# Sheme_PowerOutPut.net
KiCad netlist of a schematic drawn in Altium Designer
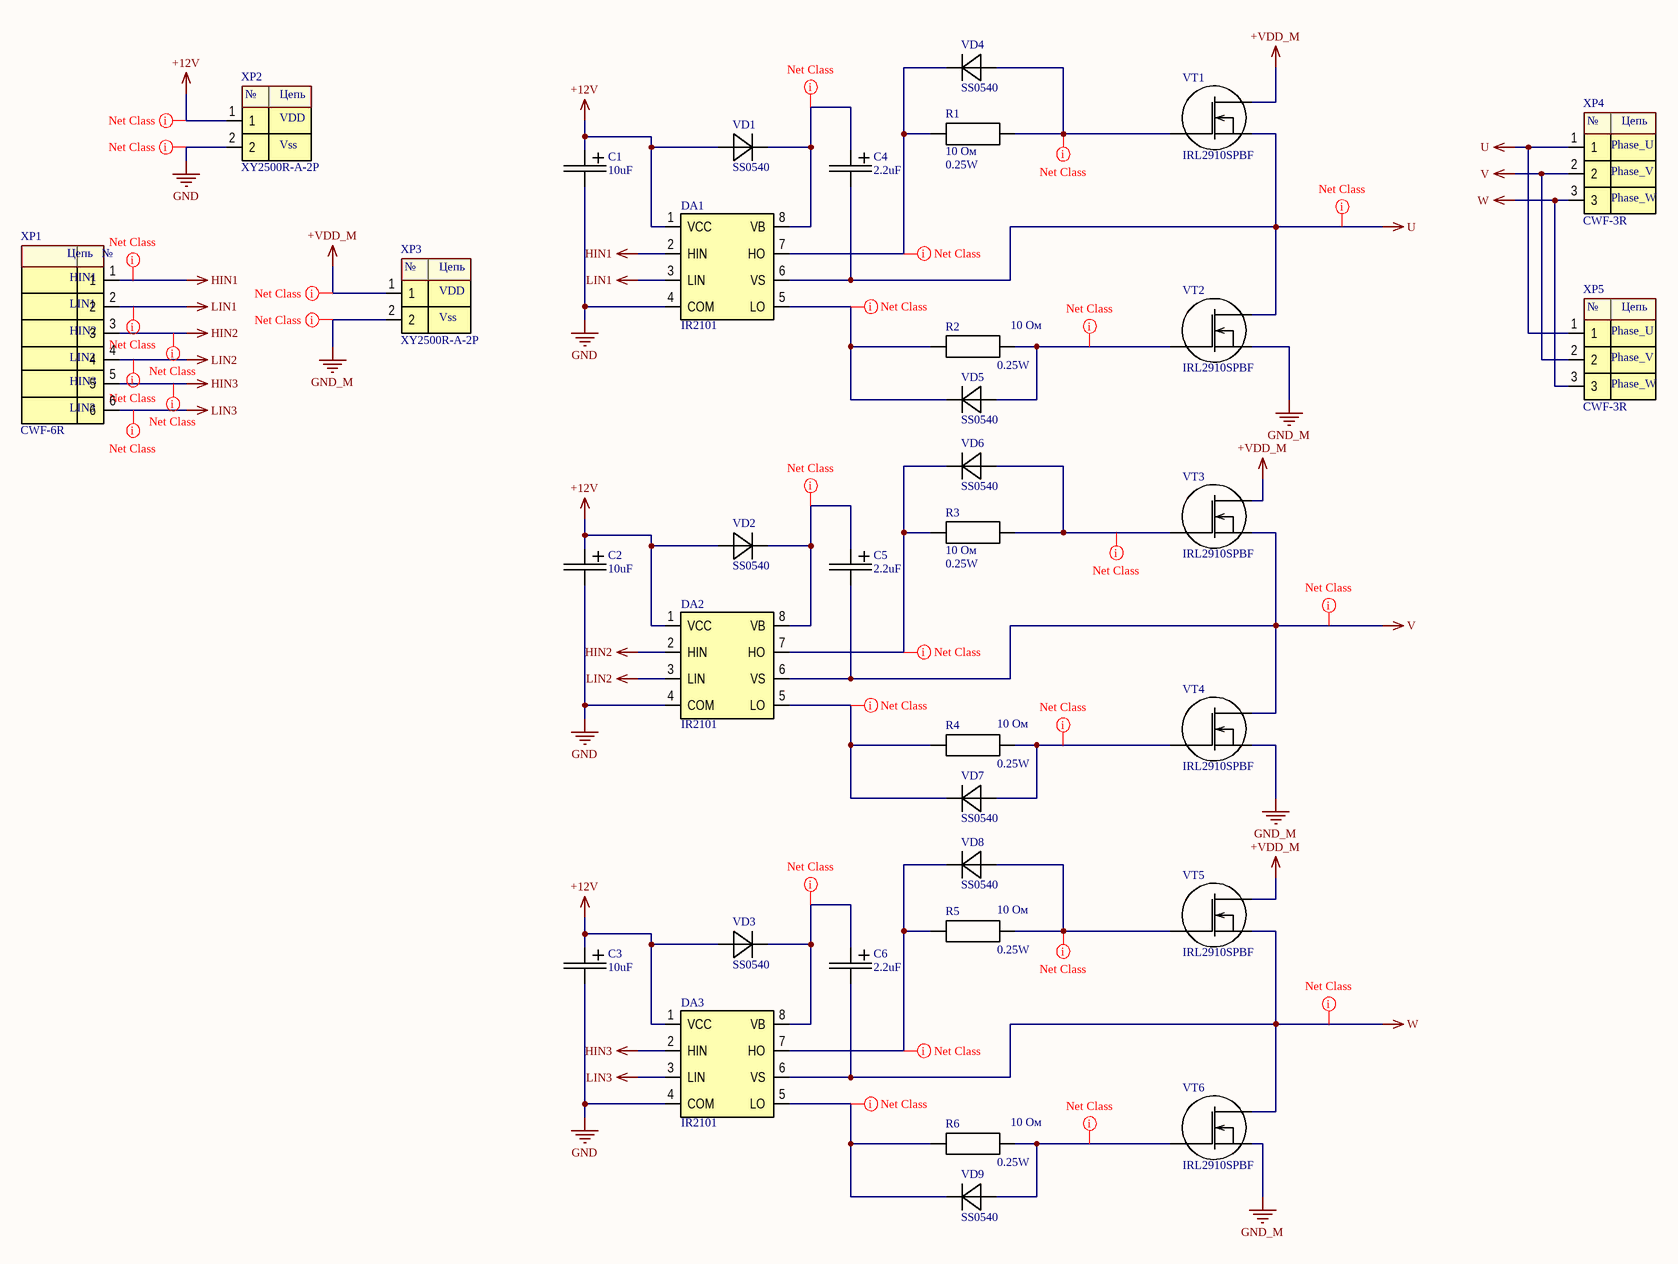
[diagram p0: Sheme_PowerOutPut.SchDoc]

(export (version "E")
  (design (tool "Eeschema 10.0.6"))
  (components
    (comp (ref "C1")
      (value "10uF")
      (footprint "CAPTtantaltypeA")
      (fields
        (field (name "PART NUMBER") "TA2u2")
        (field (name "MANUFACTURER") "Samsung")
        (field (name "POWER") "16V")
      )
      (libsource (lib "SchlibUGO") (part "Capasitor Electrolit"))
    )
    (comp (ref "C2")
      (value "10uF")
      (footprint "CAPTtantaltypeA")
      (fields
        (field (name "PART NUMBER") "TA2u2")
        (field (name "MANUFACTURER") "Samsung")
        (field (name "POWER") "16V")
      )
      (libsource (lib "SchlibUGO") (part "Capasitor Electrolit"))
    )
    (comp (ref "C3")
      (value "10uF")
      (footprint "CAPTtantaltypeA")
      (fields
        (field (name "PART NUMBER") "TA2u2")
        (field (name "MANUFACTURER") "Samsung")
        (field (name "POWER") "16V")
      )
      (libsource (lib "SchlibUGO") (part "Capasitor Electrolit"))
    )
    (comp (ref "C4")
      (value "2.2uF")
      (footprint "CAPTtantaltypeA")
      (fields
        (field (name "PART NUMBER") "TA2u2")
        (field (name "MANUFACTURER") "Samsung")
        (field (name "POWER") "16V")
      )
      (libsource (lib "SchlibUGO") (part "Capasitor Electrolit"))
    )
    (comp (ref "C5")
      (value "2.2uF")
      (footprint "CAPTtantaltypeA")
      (fields
        (field (name "PART NUMBER") "TA2u2")
        (field (name "MANUFACTURER") "Samsung")
        (field (name "POWER") "16V")
      )
      (libsource (lib "SchlibUGO") (part "Capasitor Electrolit"))
    )
    (comp (ref "C6")
      (value "2.2uF")
      (footprint "CAPTtantaltypeA")
      (fields
        (field (name "PART NUMBER") "TA2u2")
        (field (name "MANUFACTURER") "Samsung")
        (field (name "POWER") "16V")
      )
      (libsource (lib "SchlibUGO") (part "Capasitor Electrolit"))
    )
    (comp (ref "DA1")
      (value "IR2101")
      (footprint "SO-8")
      (fields (field (name "PART NUMBER") "IR2101SPBF"))
      (libsource (lib "SchlibUGO") (part "IR2101"))
    )
    (comp (ref "DA2")
      (value "IR2101")
      (footprint "SO-8")
      (fields (field (name "PART NUMBER") "IR2101SPBF"))
      (libsource (lib "SchlibUGO") (part "IR2101"))
    )
    (comp (ref "DA3")
      (value "IR2101")
      (footprint "SO-8")
      (fields (field (name "PART NUMBER") "IR2101SPBF"))
      (libsource (lib "SchlibUGO") (part "IR2101"))
    )
    (comp (ref "R1")
      (value "10 Ом")
      (footprint "1206")
      (fields
        (field (name "MANUFACTURER") "YAGEO")
        (field (name "PART NUMBER") "RC1206JR-0710RL")
        (field (name "POWER") "0.25W")
      )
      (libsource (lib "SchlibUGO") (part "Resistor"))
    )
    (comp (ref "R2")
      (value "10 Ом")
      (footprint "1206")
      (fields
        (field (name "MANUFACTURER") "YAGEO")
        (field (name "PART NUMBER") "RC1206JR-0710RL")
        (field (name "POWER") "0.25W")
      )
      (libsource (lib "SchlibUGO") (part "Resistor"))
    )
    (comp (ref "R3")
      (value "10 Ом")
      (footprint "1206")
      (fields
        (field (name "MANUFACTURER") "YAGEO")
        (field (name "PART NUMBER") "RC1206JR-0710RL")
        (field (name "POWER") "0.25W")
      )
      (libsource (lib "SchlibUGO") (part "Resistor"))
    )
    (comp (ref "R4")
      (value "10 Ом")
      (footprint "1206")
      (fields
        (field (name "MANUFACTURER") "YAGEO")
        (field (name "PART NUMBER") "RC1206JR-0710RL")
        (field (name "POWER") "0.25W")
      )
      (libsource (lib "SchlibUGO") (part "Resistor"))
    )
    (comp (ref "R5")
      (value "10 Ом")
      (footprint "1206")
      (fields
        (field (name "MANUFACTURER") "YAGEO")
        (field (name "PART NUMBER") "RC1206JR-0710RL")
        (field (name "POWER") "0.25W")
      )
      (libsource (lib "SchlibUGO") (part "Resistor"))
    )
    (comp (ref "R6")
      (value "10 Ом")
      (footprint "1206")
      (fields
        (field (name "MANUFACTURER") "YAGEO")
        (field (name "PART NUMBER") "RC1206JR-0710RL")
        (field (name "POWER") "0.25W")
      )
      (libsource (lib "SchlibUGO") (part "Resistor"))
    )
    (comp (ref "VD1")
      (value "SS0540")
      (footprint "SOD-123")
      (fields (field (name "MANUFACTURER") "DC Components"))
      (libsource (lib "SchlibUGO") (part "SS0540"))
    )
    (comp (ref "VD2")
      (value "SS0540")
      (footprint "SOD-123")
      (fields (field (name "MANUFACTURER") "DC Components"))
      (libsource (lib "SchlibUGO") (part "SS0540"))
    )
    (comp (ref "VD3")
      (value "SS0540")
      (footprint "SOD-123")
      (fields (field (name "MANUFACTURER") "DC Components"))
      (libsource (lib "SchlibUGO") (part "SS0540"))
    )
    (comp (ref "VD4")
      (value "SS0540")
      (footprint "SOD-123")
      (fields (field (name "MANUFACTURER") "DC Components"))
      (libsource (lib "SchlibUGO") (part "SS0540"))
    )
    (comp (ref "VD5")
      (value "SS0540")
      (footprint "SOD-123")
      (fields (field (name "MANUFACTURER") "DC Components"))
      (libsource (lib "SchlibUGO") (part "SS0540"))
    )
    (comp (ref "VD6")
      (value "SS0540")
      (footprint "SOD-123")
      (fields (field (name "MANUFACTURER") "DC Components"))
      (libsource (lib "SchlibUGO") (part "SS0540"))
    )
    (comp (ref "VD7")
      (value "SS0540")
      (footprint "SOD-123")
      (fields (field (name "MANUFACTURER") "DC Components"))
      (libsource (lib "SchlibUGO") (part "SS0540"))
    )
    (comp (ref "VD8")
      (value "SS0540")
      (footprint "SOD-123")
      (fields (field (name "MANUFACTURER") "DC Components"))
      (libsource (lib "SchlibUGO") (part "SS0540"))
    )
    (comp (ref "VD9")
      (value "SS0540")
      (footprint "SOD-123")
      (fields (field (name "MANUFACTURER") "DC Components"))
      (libsource (lib "SchlibUGO") (part "SS0540"))
    )
    (comp (ref "VT1")
      (value "IRL2910SPBF")
      (footprint "D2PACK")
      (fields (field (name "MANUFACTURER") "International rectifier"))
      (libsource (lib "SchlibUGO") (part "IRL2910SPBF"))
    )
    (comp (ref "VT2")
      (value "IRL2910SPBF")
      (footprint "D2PACK")
      (fields (field (name "MANUFACTURER") "International rectifier"))
      (libsource (lib "SchlibUGO") (part "IRL2910SPBF"))
    )
    (comp (ref "VT3")
      (value "IRL2910SPBF")
      (footprint "D2PACK")
      (fields (field (name "MANUFACTURER") "International rectifier"))
      (libsource (lib "SchlibUGO") (part "IRL2910SPBF"))
    )
    (comp (ref "VT4")
      (value "IRL2910SPBF")
      (footprint "D2PACK")
      (fields (field (name "MANUFACTURER") "International rectifier"))
      (libsource (lib "SchlibUGO") (part "IRL2910SPBF"))
    )
    (comp (ref "VT5")
      (value "IRL2910SPBF")
      (footprint "D2PACK")
      (fields (field (name "MANUFACTURER") "International rectifier"))
      (libsource (lib "SchlibUGO") (part "IRL2910SPBF"))
    )
    (comp (ref "VT6")
      (value "IRL2910SPBF")
      (footprint "D2PACK")
      (fields (field (name "MANUFACTURER") "International rectifier"))
      (libsource (lib "SchlibUGO") (part "IRL2910SPBF"))
    )
    (comp (ref "XP1")
      (value "CWF-6R")
      (footprint "CWF-6R")
      (fields (field (name "MANUFACTURER") "KLS"))
      (libsource (lib "SchlibUGO") (part "CWF-6R"))
    )
    (comp (ref "XP2")
      (value "XY2500R-A-2P")
      (footprint "KLS2-EDR-500-2P")
      (fields (field (name "MANUFACTURER") "RoB"))
      (libsource (lib "SchlibUGO") (part "Connector_Power"))
    )
    (comp (ref "XP3")
      (value "XY2500R-A-2P")
      (footprint "KLS2-EDR-500-2P")
      (fields (field (name "MANUFACTURER") "RoB"))
      (libsource (lib "SchlibUGO") (part "Connector_Power"))
    )
    (comp (ref "XP4")
      (value "CWF-3R")
      (footprint "CWF-3R")
      (fields (field (name "MANUFACTURER") "KLS"))
      (libsource (lib "SchlibUGO") (part "CWF-3R"))
    )
    (comp (ref "XP5")
      (value "CWF-3R")
      (footprint "CWF-3R")
      (fields (field (name "MANUFACTURER") "KLS"))
      (libsource (lib "SchlibUGO") (part "CWF-3R"))
    )
  )
  (nets
    (net (code "1") (name "+12V") (class "Default")
      (node (ref "C1") (pin "1") (pinfunction "1_1") (pintype "passive"))
      (node (ref "C2") (pin "1") (pinfunction "1_1") (pintype "passive"))
      (node (ref "C3") (pin "1") (pinfunction "1_1") (pintype "passive"))
      (node (ref "DA1") (pin "1") (pinfunction "VCC_1") (pintype "passive"))
      (node (ref "DA2") (pin "1") (pinfunction "VCC_1") (pintype "passive"))
      (node (ref "DA3") (pin "1") (pinfunction "VCC_1") (pintype "passive"))
      (node (ref "VD1") (pin "1") (pinfunction "1_1") (pintype "passive"))
      (node (ref "VD2") (pin "1") (pinfunction "1_1") (pintype "passive"))
      (node (ref "VD3") (pin "1") (pinfunction "1_1") (pintype "passive"))
      (node (ref "XP2") (pin "1") (pinfunction "1_1") (pintype "passive"))
    )
    (net (code "2") (name "+VDD_M") (class "Default")
      (node (ref "VT1") (pin "2") (pinfunction "D_2") (pintype "passive"))
      (node (ref "VT3") (pin "2") (pinfunction "D_2") (pintype "passive"))
      (node (ref "VT5") (pin "2") (pinfunction "D_2") (pintype "passive"))
      (node (ref "XP3") (pin "1") (pinfunction "1_1") (pintype "passive"))
    )
    (net (code "3") (name "GND") (class "Default")
      (node (ref "C1") (pin "2") (pinfunction "2_2") (pintype "passive"))
      (node (ref "C2") (pin "2") (pinfunction "2_2") (pintype "passive"))
      (node (ref "C3") (pin "2") (pinfunction "2_2") (pintype "passive"))
      (node (ref "DA1") (pin "4") (pinfunction "COM_4") (pintype "passive"))
      (node (ref "DA2") (pin "4") (pinfunction "COM_4") (pintype "passive"))
      (node (ref "DA3") (pin "4") (pinfunction "COM_4") (pintype "passive"))
      (node (ref "XP2") (pin "2") (pinfunction "2_2") (pintype "passive"))
    )
    (net (code "4") (name "GND_M") (class "Default")
      (node (ref "VT2") (pin "3") (pinfunction "Source_3") (pintype "passive"))
      (node (ref "VT4") (pin "3") (pinfunction "Source_3") (pintype "passive"))
      (node (ref "VT6") (pin "3") (pinfunction "Source_3") (pintype "passive"))
      (node (ref "XP3") (pin "2") (pinfunction "2_2") (pintype "passive"))
    )
    (net (code "5") (name "HIN1") (class "Default")
      (node (ref "DA1") (pin "2") (pinfunction "HIN_2") (pintype "passive"))
      (node (ref "XP1") (pin "1") (pinfunction "1_1") (pintype "passive"))
    )
    (net (code "6") (name "HIN2") (class "Default")
      (node (ref "DA2") (pin "2") (pinfunction "HIN_2") (pintype "passive"))
      (node (ref "XP1") (pin "3") (pinfunction "3_3") (pintype "passive"))
    )
    (net (code "7") (name "HIN3") (class "Default")
      (node (ref "DA3") (pin "2") (pinfunction "HIN_2") (pintype "passive"))
      (node (ref "XP1") (pin "5") (pinfunction "5_5") (pintype "passive"))
    )
    (net (code "8") (name "LIN1") (class "Default")
      (node (ref "DA1") (pin "3") (pinfunction "LIN_3") (pintype "passive"))
      (node (ref "XP1") (pin "2") (pinfunction "2_2") (pintype "passive"))
    )
    (net (code "9") (name "LIN2") (class "Default")
      (node (ref "DA2") (pin "3") (pinfunction "LIN_3") (pintype "passive"))
      (node (ref "XP1") (pin "4") (pinfunction "4_4") (pintype "passive"))
    )
    (net (code "10") (name "LIN3") (class "Default")
      (node (ref "DA3") (pin "3") (pinfunction "LIN_3") (pintype "passive"))
      (node (ref "XP1") (pin "6") (pinfunction "6_6") (pintype "passive"))
    )
    (net (code "11") (name "Net-(DA1-HO)") (class "Default")
      (node (ref "DA1") (pin "7") (pinfunction "HO_7") (pintype "passive"))
      (node (ref "R1") (pin "1") (pinfunction "1_1") (pintype "passive"))
      (node (ref "VD4") (pin "2") (pinfunction "2_2") (pintype "passive"))
    )
    (net (code "12") (name "Net-(DA1-LO)") (class "Default")
      (node (ref "DA1") (pin "5") (pinfunction "LO_5") (pintype "passive"))
      (node (ref "R2") (pin "1") (pinfunction "1_1") (pintype "passive"))
      (node (ref "VD5") (pin "2") (pinfunction "2_2") (pintype "passive"))
    )
    (net (code "13") (name "Net-(DA1-VB)") (class "Default")
      (node (ref "C4") (pin "1") (pinfunction "1_1") (pintype "passive"))
      (node (ref "DA1") (pin "8") (pinfunction "VB_8") (pintype "passive"))
      (node (ref "VD1") (pin "2") (pinfunction "2_2") (pintype "passive"))
    )
    (net (code "14") (name "Net-(DA2-HO)") (class "Default")
      (node (ref "DA2") (pin "7") (pinfunction "HO_7") (pintype "passive"))
      (node (ref "R3") (pin "1") (pinfunction "1_1") (pintype "passive"))
      (node (ref "VD6") (pin "2") (pinfunction "2_2") (pintype "passive"))
    )
    (net (code "15") (name "Net-(DA2-LO)") (class "Default")
      (node (ref "DA2") (pin "5") (pinfunction "LO_5") (pintype "passive"))
      (node (ref "R4") (pin "1") (pinfunction "1_1") (pintype "passive"))
      (node (ref "VD7") (pin "2") (pinfunction "2_2") (pintype "passive"))
    )
    (net (code "16") (name "Net-(DA2-VB)") (class "Default")
      (node (ref "C5") (pin "1") (pinfunction "1_1") (pintype "passive"))
      (node (ref "DA2") (pin "8") (pinfunction "VB_8") (pintype "passive"))
      (node (ref "VD2") (pin "2") (pinfunction "2_2") (pintype "passive"))
    )
    (net (code "17") (name "Net-(DA3-HO)") (class "Default")
      (node (ref "DA3") (pin "7") (pinfunction "HO_7") (pintype "passive"))
      (node (ref "R5") (pin "1") (pinfunction "1_1") (pintype "passive"))
      (node (ref "VD8") (pin "2") (pinfunction "2_2") (pintype "passive"))
    )
    (net (code "18") (name "Net-(DA3-LO)") (class "Default")
      (node (ref "DA3") (pin "5") (pinfunction "LO_5") (pintype "passive"))
      (node (ref "R6") (pin "1") (pinfunction "1_1") (pintype "passive"))
      (node (ref "VD9") (pin "2") (pinfunction "2_2") (pintype "passive"))
    )
    (net (code "19") (name "Net-(DA3-VB)") (class "Default")
      (node (ref "C6") (pin "1") (pinfunction "1_1") (pintype "passive"))
      (node (ref "DA3") (pin "8") (pinfunction "VB_8") (pintype "passive"))
      (node (ref "VD3") (pin "2") (pinfunction "2_2") (pintype "passive"))
    )
    (net (code "20") (name "Net-(VT1-G)") (class "Default")
      (node (ref "R1") (pin "2") (pinfunction "2_2") (pintype "passive"))
      (node (ref "VD4") (pin "1") (pinfunction "1_1") (pintype "passive"))
      (node (ref "VT1") (pin "1") (pinfunction "G_1") (pintype "passive"))
    )
    (net (code "21") (name "Net-(VT2-G)") (class "Default")
      (node (ref "R2") (pin "2") (pinfunction "2_2") (pintype "passive"))
      (node (ref "VD5") (pin "1") (pinfunction "1_1") (pintype "passive"))
      (node (ref "VT2") (pin "1") (pinfunction "G_1") (pintype "passive"))
    )
    (net (code "22") (name "Net-(VT3-G)") (class "Default")
      (node (ref "R3") (pin "2") (pinfunction "2_2") (pintype "passive"))
      (node (ref "VD6") (pin "1") (pinfunction "1_1") (pintype "passive"))
      (node (ref "VT3") (pin "1") (pinfunction "G_1") (pintype "passive"))
    )
    (net (code "23") (name "Net-(VT4-G)") (class "Default")
      (node (ref "R4") (pin "2") (pinfunction "2_2") (pintype "passive"))
      (node (ref "VD7") (pin "1") (pinfunction "1_1") (pintype "passive"))
      (node (ref "VT4") (pin "1") (pinfunction "G_1") (pintype "passive"))
    )
    (net (code "24") (name "Net-(VT5-G)") (class "Default")
      (node (ref "R5") (pin "2") (pinfunction "2_2") (pintype "passive"))
      (node (ref "VD8") (pin "1") (pinfunction "1_1") (pintype "passive"))
      (node (ref "VT5") (pin "1") (pinfunction "G_1") (pintype "passive"))
    )
    (net (code "25") (name "Net-(VT6-G)") (class "Default")
      (node (ref "R6") (pin "2") (pinfunction "2_2") (pintype "passive"))
      (node (ref "VD9") (pin "1") (pinfunction "1_1") (pintype "passive"))
      (node (ref "VT6") (pin "1") (pinfunction "G_1") (pintype "passive"))
    )
    (net (code "26") (name "U") (class "Default")
      (node (ref "C4") (pin "2") (pinfunction "2_2") (pintype "passive"))
      (node (ref "DA1") (pin "6") (pinfunction "VS_6") (pintype "passive"))
      (node (ref "VT1") (pin "3") (pinfunction "Source_3") (pintype "passive"))
      (node (ref "VT2") (pin "2") (pinfunction "D_2") (pintype "passive"))
      (node (ref "XP4") (pin "1") (pinfunction "1_1") (pintype "passive"))
      (node (ref "XP5") (pin "1") (pinfunction "1_1") (pintype "passive"))
    )
    (net (code "27") (name "V") (class "Default")
      (node (ref "C5") (pin "2") (pinfunction "2_2") (pintype "passive"))
      (node (ref "DA2") (pin "6") (pinfunction "VS_6") (pintype "passive"))
      (node (ref "VT3") (pin "3") (pinfunction "Source_3") (pintype "passive"))
      (node (ref "VT4") (pin "2") (pinfunction "D_2") (pintype "passive"))
      (node (ref "XP4") (pin "2") (pinfunction "2_2") (pintype "passive"))
      (node (ref "XP5") (pin "2") (pinfunction "2_2") (pintype "passive"))
    )
    (net (code "28") (name "W") (class "Default")
      (node (ref "C6") (pin "2") (pinfunction "2_2") (pintype "passive"))
      (node (ref "DA3") (pin "6") (pinfunction "VS_6") (pintype "passive"))
      (node (ref "VT5") (pin "3") (pinfunction "Source_3") (pintype "passive"))
      (node (ref "VT6") (pin "2") (pinfunction "D_2") (pintype "passive"))
      (node (ref "XP4") (pin "3") (pinfunction "3_3") (pintype "passive"))
      (node (ref "XP5") (pin "3") (pinfunction "3_3") (pintype "passive"))
    )
  )
)
